# io_sensor.net
KiCad netlist of a schematic drawn in Altium Designer
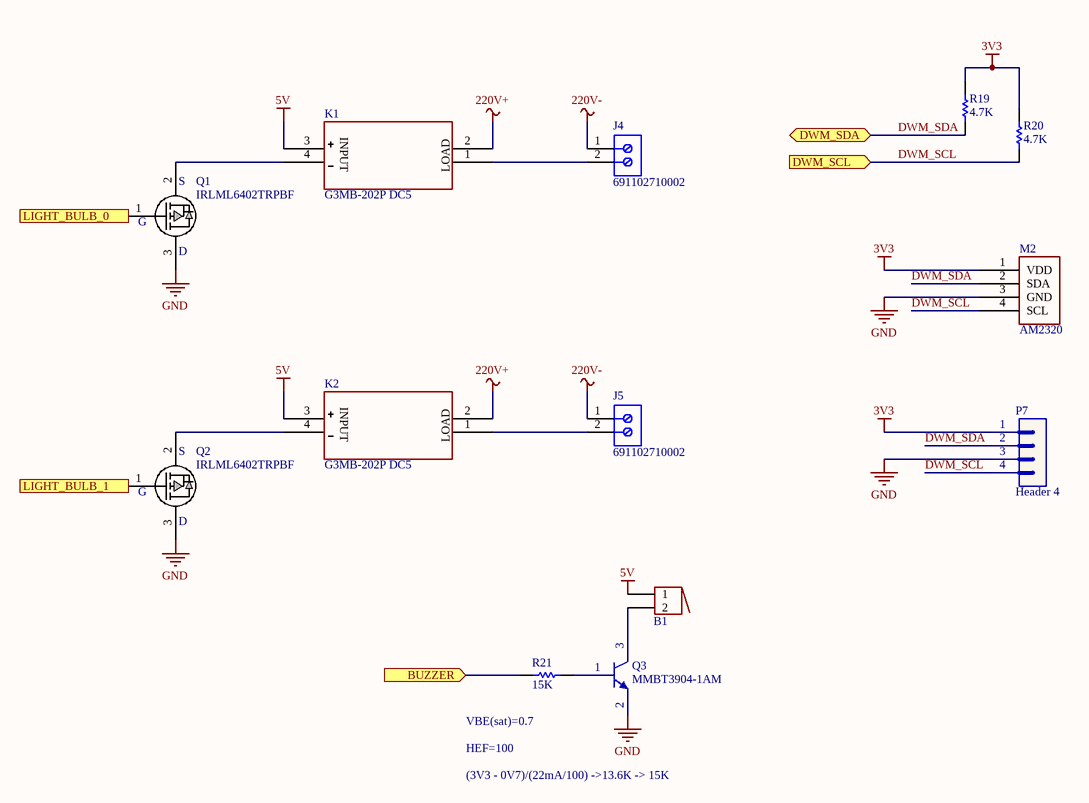
[diagram p0: io_sensor.SchDoc]

(export (version "E")
  (design (tool "Eeschema 10.0.6"))
  (components
    (comp (ref "B1")
      (value "Buzzer")
      (footprint "BUZZER")
      (fields (field (name "LOCAL SUPPLIER PART NUMBER") "1209 DIP Buzzer 12x9mm"))
      (libsource (lib "miscellaneous") (part "Buzzer"))
    )
    (comp (ref "J4")
      (value "691102710002")
      (footprint "691102710002")
      (description "WR-TBL Serie 102 Horizontal Entry Modular, Pressure Clamp, pitch 5mm, 2p")
      (fields (field (name "PUBLISHER") "Wurth Elektronik"))
      (libsource (lib "domino-wire-protector") (part "691102710002"))
    )
    (comp (ref "J5")
      (value "691102710002")
      (footprint "691102710002")
      (description "WR-TBL Serie 102 Horizontal Entry Modular, Pressure Clamp, pitch 5mm, 2p")
      (fields (field (name "PUBLISHER") "Wurth Elektronik"))
      (libsource (lib "domino-wire-protector") (part "691102710002"))
    )
    (comp (ref "K1")
      (value "G3MB-202P DC5")
      (footprint "G3MB")
      (description "5VDC-220VAC Solid State Relay")
      (fields (field (name "COPYRIGHT") "Copyright (C) 2018 Accelerated Designs. All rights reserved"))
      (libsource (lib "relay") (part "G3MB-202P DC5"))
    )
    (comp (ref "K2")
      (value "G3MB-202P DC5")
      (footprint "G3MB")
      (description "5VDC-220VAC Solid State Relay")
      (fields (field (name "COPYRIGHT") "Copyright (C) 2018 Accelerated Designs. All rights reserved"))
      (libsource (lib "relay") (part "G3MB-202P DC5"))
    )
    (comp (ref "M2") (value "AM2320") (footprint "AM2320") (libsource (lib "module") (part "AM2320")))
    (comp (ref "P7")
      (value "Header 4")
      (footprint "JP4")
      (description "Header, 4-Pin")
      (fields (field (name "LOCAL SUPPLIER PART NUMBER") "x") (field (name "PUBLISHER") "Altium Limited"))
      (libsource (lib "header-connector") (part "Header 4"))
    )
    (comp (ref "Q1")
      (value "IRLML6402TRPBF")
      (footprint "SOT23_NEX")
      (description "P-Channel 20V 3.7A (Ta) 1.3W (Ta) Surface Mount Micro3™/SOT-23")
      (libsource (lib "mosfet-smd") (part "IRLML6402TRPBF"))
    )
    (comp (ref "Q2")
      (value "IRLML6402TRPBF")
      (footprint "SOT23_NEX")
      (description "P-Channel 20V 3.7A (Ta) 1.3W (Ta) Surface Mount Micro3™/SOT-23")
      (libsource (lib "mosfet-smd") (part "IRLML6402TRPBF"))
    )
    (comp (ref "Q3")
      (value "MMBT3904-1AM")
      (footprint "SOT23_NEX")
      (libsource (lib "bjt-smd") (part "MMBT3904-1AM"))
    )
    (comp (ref "R19")
      (value "4.7K")
      (footprint "resistor-smd:RES-SM-0805")
      (description "RES SMD 4.7K OHM 5% 1/8W 0805")
      (fields
        (field (name "MANUFACTURER") "Yageo")
        (field (name "MANUFACTURER PART NUMBER") "RC0805JR-074K7L")
      )
      (libsource (lib "resistor-smd") (part "Res-4.7K-0805"))
    )
    (comp (ref "R20")
      (value "4.7K")
      (footprint "resistor-smd:RES-SM-0805")
      (description "RES SMD 4.7K OHM 5% 1/8W 0805")
      (fields
        (field (name "MANUFACTURER") "Yageo")
        (field (name "MANUFACTURER PART NUMBER") "RC0805JR-074K7L")
      )
      (libsource (lib "resistor-smd") (part "Res-4.7K-0805"))
    )
    (comp (ref "R21")
      (value "15K")
      (footprint "resistor-smd:RES-SM-0805")
      (description "RES 15K OHM 1% 1/4W 0805")
      (fields
        (field (name "MANUFACTURER") "TE Connectivity Passive Product")
        (field (name "MANUFACTURER PART NUMBER") "CRGCQ0805F15K")
      )
      (libsource (lib "resistor-smd") (part "Res-15K-0805"))
    )
  )
  (nets
    (net (code "1") (name "/BUZZER") (class "Default")
      (node (ref "R21") (pin "1") (pinfunction "1_1") (pintype "passive"))
    )
    (net (code "2") (name "/DWM_SCL") (class "Default")
      (node (ref "M2") (pin "4") (pinfunction "SCL_4") (pintype "passive"))
      (node (ref "P7") (pin "4") (pinfunction "4_4") (pintype "passive"))
      (node (ref "R20") (pin "1") (pinfunction "1_1") (pintype "passive"))
    )
    (net (code "3") (name "/DWM_SDA") (class "Default")
      (node (ref "M2") (pin "2") (pinfunction "SDA_2") (pintype "passive"))
      (node (ref "P7") (pin "2") (pinfunction "2_2") (pintype "passive"))
      (node (ref "R19") (pin "1") (pinfunction "1_1") (pintype "passive"))
    )
    (net (code "4") (name "/LIGHT_BULB_0") (class "Default")
      (node (ref "Q1") (pin "1") (pinfunction "G_1") (pintype "passive"))
    )
    (net (code "5") (name "/LIGHT_BULB_1") (class "Default")
      (node (ref "Q2") (pin "1") (pinfunction "G_1") (pintype "passive"))
    )
    (net (code "6") (name "3V3") (class "Default")
      (node (ref "M2") (pin "1") (pinfunction "VDD_1") (pintype "passive"))
      (node (ref "P7") (pin "1") (pinfunction "1_1") (pintype "passive"))
      (node (ref "R19") (pin "2") (pinfunction "2_2") (pintype "passive"))
      (node (ref "R20") (pin "2") (pinfunction "2_2") (pintype "passive"))
    )
    (net (code "7") (name "5V") (class "Default")
      (node (ref "B1") (pin "1") (pinfunction "1_1") (pintype "passive"))
      (node (ref "K1") (pin "3") (pinfunction "3_3") (pintype "passive"))
      (node (ref "K2") (pin "3") (pinfunction "3_3") (pintype "passive"))
    )
    (net (code "8") (name "220V+") (class "Default")
      (node (ref "K1") (pin "2") (pinfunction "2_2") (pintype "passive"))
      (node (ref "K2") (pin "2") (pinfunction "2_2") (pintype "passive"))
    )
    (net (code "9") (name "220V-") (class "Default")
      (node (ref "J4") (pin "1") (pinfunction "1_1") (pintype "passive"))
      (node (ref "J5") (pin "1") (pinfunction "1_1") (pintype "passive"))
    )
    (net (code "10") (name "GND") (class "Default")
      (node (ref "M2") (pin "3") (pinfunction "GND_3") (pintype "passive"))
      (node (ref "P7") (pin "3") (pinfunction "3_3") (pintype "passive"))
      (node (ref "Q1") (pin "3") (pinfunction "D_3") (pintype "passive"))
      (node (ref "Q2") (pin "3") (pinfunction "D_3") (pintype "passive"))
      (node (ref "Q3") (pin "2") (pinfunction "E_2") (pintype "passive"))
    )
    (net (code "11") (name "Net-(J4-Pad2)") (class "Default")
      (node (ref "J4") (pin "2") (pinfunction "2_2") (pintype "passive"))
      (node (ref "K1") (pin "1") (pinfunction "1_1") (pintype "passive"))
    )
    (net (code "12") (name "Net-(J5-Pad2)") (class "Default")
      (node (ref "J5") (pin "2") (pinfunction "2_2") (pintype "passive"))
      (node (ref "K2") (pin "1") (pinfunction "1_1") (pintype "passive"))
    )
    (net (code "13") (name "Net-(Q1-S)") (class "Default")
      (node (ref "K1") (pin "4") (pinfunction "4_4") (pintype "passive"))
      (node (ref "Q1") (pin "2") (pinfunction "S_2") (pintype "passive"))
    )
    (net (code "14") (name "Net-(Q2-S)") (class "Default")
      (node (ref "K2") (pin "4") (pinfunction "4_4") (pintype "passive"))
      (node (ref "Q2") (pin "2") (pinfunction "S_2") (pintype "passive"))
    )
    (net (code "15") (name "Net-(Q3-B)") (class "Default")
      (node (ref "Q3") (pin "1") (pinfunction "B_1") (pintype "passive"))
      (node (ref "R21") (pin "2") (pinfunction "2_2") (pintype "passive"))
    )
    (net (code "16") (name "Net-(Q3-C)") (class "Default")
      (node (ref "B1") (pin "2") (pinfunction "2_2") (pintype "passive"))
      (node (ref "Q3") (pin "3") (pinfunction "C_3") (pintype "passive"))
    )
  )
)
